# 2_-MCU_LPC1778FBD144.net
KiCad netlist of a schematic drawn in Altium Designer
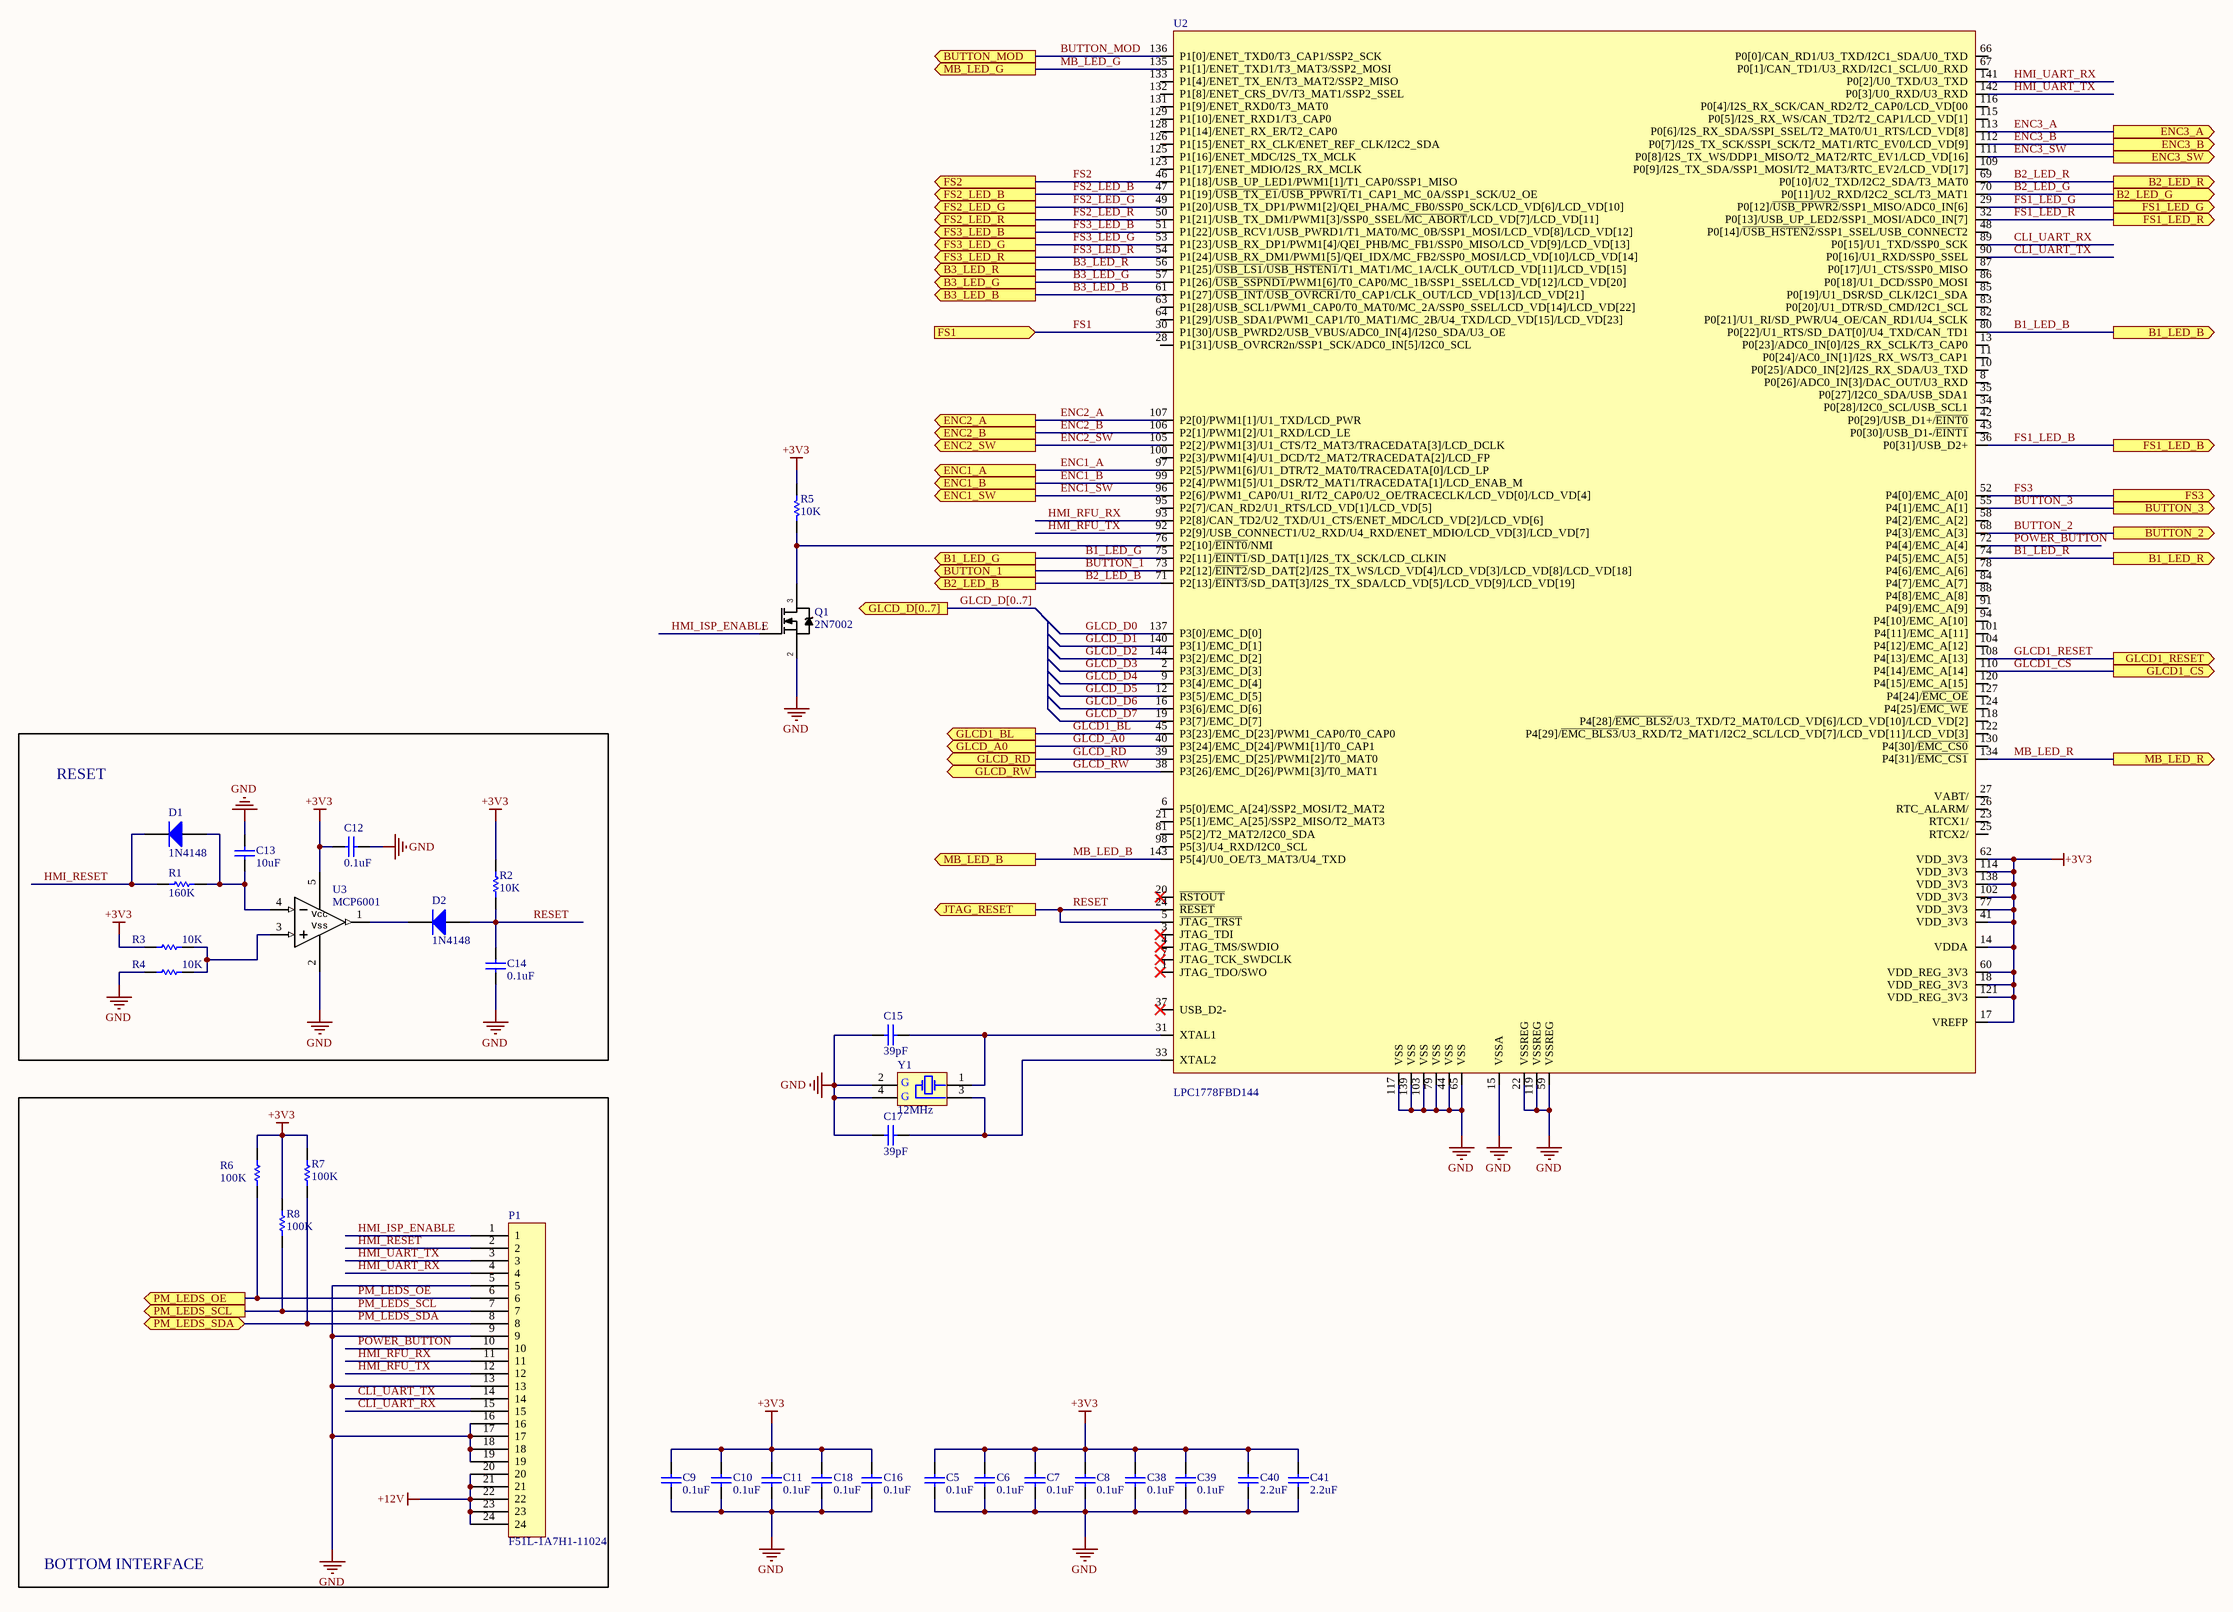
[diagram p0: [2]-MCU_LPC1778FBD144.SchDoc]

(export (version "E")
  (design (tool "Eeschema 10.0.6"))
  (components
    (comp (ref "C5")
      (value "0.1uF")
      (footprint "CAPC1608N")
      (description "CAP CER 0.1UF 25V X7R 0603")
      (fields (field (name "TOLERANCE") "10%") (field (name "VOLTAGE") "25V"))
      (libsource (lib "bitsnio") (part "CC0603KRX7R8BB104"))
    )
    (comp (ref "C6")
      (value "0.1uF")
      (footprint "CAPC1608N")
      (description "CAP CER 0.1UF 25V X7R 0603")
      (fields (field (name "TOLERANCE") "10%") (field (name "VOLTAGE") "25V"))
      (libsource (lib "bitsnio") (part "CC0603KRX7R8BB104"))
    )
    (comp (ref "C7")
      (value "0.1uF")
      (footprint "CAPC1608N")
      (description "CAP CER 0.1UF 25V X7R 0603")
      (fields (field (name "TOLERANCE") "10%") (field (name "VOLTAGE") "25V"))
      (libsource (lib "bitsnio") (part "CC0603KRX7R8BB104"))
    )
    (comp (ref "C8")
      (value "0.1uF")
      (footprint "CAPC1608N")
      (description "CAP CER 0.1UF 25V X7R 0603")
      (fields (field (name "TOLERANCE") "10%") (field (name "VOLTAGE") "25V"))
      (libsource (lib "bitsnio") (part "CC0603KRX7R8BB104"))
    )
    (comp (ref "C9")
      (value "0.1uF")
      (footprint "CAPC1608N")
      (description "CAP CER 0.1UF 25V X7R 0603")
      (fields (field (name "TOLERANCE") "10%") (field (name "VOLTAGE") "25V"))
      (libsource (lib "bitsnio") (part "CC0603KRX7R8BB104"))
    )
    (comp (ref "C10")
      (value "0.1uF")
      (footprint "CAPC1608N")
      (description "CAP CER 0.1UF 25V X7R 0603")
      (fields (field (name "TOLERANCE") "10%") (field (name "VOLTAGE") "25V"))
      (libsource (lib "bitsnio") (part "CC0603KRX7R8BB104"))
    )
    (comp (ref "C11")
      (value "0.1uF")
      (footprint "CAPC1608N")
      (description "CAP CER 0.1UF 25V X7R 0603")
      (fields (field (name "TOLERANCE") "10%") (field (name "VOLTAGE") "25V"))
      (libsource (lib "bitsnio") (part "CC0603KRX7R8BB104"))
    )
    (comp (ref "C12")
      (value "0.1uF")
      (footprint "CAPC1608N")
      (description "CAP CER 0.1UF 25V X7R 0603")
      (fields (field (name "TOLERANCE") "10%") (field (name "VOLTAGE") "25V"))
      (libsource (lib "bitsnio") (part "CC0603KRX7R8BB104"))
    )
    (comp (ref "C13")
      (value "10uF")
      (footprint "CAPC1608N")
      (description "CAP CER 10UF 10V X5R 0603")
      (fields (field (name "TOLERANCE") "10%") (field (name "VOLTAGE") "10V"))
      (libsource (lib "bitsnio") (part "GRM188R61A106KE69D"))
    )
    (comp (ref "C14")
      (value "0.1uF")
      (footprint "CAPC1608N")
      (description "CAP CER 0.1UF 25V X7R 0603")
      (fields (field (name "TOLERANCE") "10%") (field (name "VOLTAGE") "25V"))
      (libsource (lib "bitsnio") (part "CC0603KRX7R8BB104"))
    )
    (comp (ref "C15")
      (value "39pF")
      (footprint "CAPC1608N")
      (description "CAP CER 39PF 50V NP0 0603")
      (fields (field (name "TOLERANCE") "5%"))
      (libsource (lib "bitsnio") (part "C1608NP01H390J080AA"))
    )
    (comp (ref "C16")
      (value "0.1uF")
      (footprint "CAPC1608N")
      (description "CAP CER 0.1UF 25V X7R 0603")
      (fields (field (name "TOLERANCE") "10%") (field (name "VOLTAGE") "25V"))
      (libsource (lib "bitsnio") (part "CC0603KRX7R8BB104"))
    )
    (comp (ref "C17")
      (value "39pF")
      (footprint "CAPC1608N")
      (description "CAP CER 39PF 50V NP0 0603")
      (fields (field (name "TOLERANCE") "5%"))
      (libsource (lib "bitsnio") (part "C1608NP01H390J080AA"))
    )
    (comp (ref "C18")
      (value "0.1uF")
      (footprint "CAPC1608N")
      (description "CAP CER 0.1UF 25V X7R 0603")
      (fields (field (name "TOLERANCE") "10%") (field (name "VOLTAGE") "25V"))
      (libsource (lib "bitsnio") (part "CC0603KRX7R8BB104"))
    )
    (comp (ref "C38")
      (value "0.1uF")
      (footprint "CAPC1608N")
      (description "CAP CER 0.1UF 25V X7R 0603")
      (fields (field (name "TOLERANCE") "10%") (field (name "VOLTAGE") "25V"))
      (libsource (lib "bitsnio") (part "CC0603KRX7R8BB104"))
    )
    (comp (ref "C39")
      (value "0.1uF")
      (footprint "CAPC1608N")
      (description "CAP CER 0.1UF 25V X7R 0603")
      (fields (field (name "TOLERANCE") "10%") (field (name "VOLTAGE") "25V"))
      (libsource (lib "bitsnio") (part "CC0603KRX7R8BB104"))
    )
    (comp (ref "C40")
      (value "2.2uF")
      (footprint "CAPC1608N")
      (description "CAP CER 2.2UF 10V X5R 0603")
      (fields (field (name "MANUFACTURER PART NUMBER") "CL10A225KP8NNNC") (field (name "TOLERANCE") "10%"))
      (libsource (lib "bitsnio") (part "CL10A225KP8NNNC"))
    )
    (comp (ref "C41")
      (value "2.2uF")
      (footprint "CAPC1608N")
      (description "CAP CER 2.2UF 10V X5R 0603")
      (fields (field (name "MANUFACTURER PART NUMBER") "CL10A225KP8NNNC") (field (name "TOLERANCE") "10%"))
      (libsource (lib "bitsnio") (part "CL10A225KP8NNNC"))
    )
    (comp (ref "D1")
      (value "1N4148")
      (footprint "SOD-323")
      (description "DIODE SWITCHING 75V 0.15A SOD323")
      (fields (field (name "VOLTAGE") "75V"))
      (libsource (lib "bitsnio") (part "1N4148WS-7-F"))
    )
    (comp (ref "D2")
      (value "1N4148")
      (footprint "SOD-323")
      (description "DIODE SWITCHING 75V 0.15A SOD323")
      (fields (field (name "VOLTAGE") "75V"))
      (libsource (lib "bitsnio") (part "1N4148WS-7-F"))
    )
    (comp (ref "P1")
      (value "F51L-1A7H1-11024")
      (footprint "F51L-1A7H1-11024")
      (description "FLEX CONNECTOR, 1.00MM PITCH, HE")
      (libsource (lib "bitsnio") (part "F51L-1A7H1-11024"))
    )
    (comp (ref "Q1")
      (value "2N7002")
      (footprint "SOT23-3N")
      (description "MOSFET N-CH 60V 115MA SOT-23")
      (fields (field (name "VOLTAGE") "60V"))
      (libsource (lib "bitsnio") (part "2N7002"))
    )
    (comp (ref "R1")
      (value "160K")
      (footprint "RESC1608N")
      (description "RES SMD 160K OHM 5% 1/10W 0603")
      (fields (field (name "TOLERANCE") "5%"))
      (libsource (lib "bitsnio") (part "RMCF0603JT160K"))
    )
    (comp (ref "R2")
      (value "10K")
      (footprint "RESC1608N")
      (description "RES SMD 10K OHM 5% 1/10W 0603")
      (fields (field (name "TOLERANCE") "5%"))
      (libsource (lib "bitsnio") (part "AC0603JR-0710KL"))
    )
    (comp (ref "R3")
      (value "10K")
      (footprint "RESC1608N")
      (description "RES SMD 10K OHM 5% 1/10W 0603")
      (fields (field (name "TOLERANCE") "5%"))
      (libsource (lib "bitsnio") (part "AC0603JR-0710KL"))
    )
    (comp (ref "R4")
      (value "10K")
      (footprint "RESC1608N")
      (description "RES SMD 10K OHM 5% 1/10W 0603")
      (fields (field (name "TOLERANCE") "5%"))
      (libsource (lib "bitsnio") (part "AC0603JR-0710KL"))
    )
    (comp (ref "R5")
      (value "10K")
      (footprint "RESC1608N")
      (description "RES SMD 10K OHM 5% 1/10W 0603")
      (fields (field (name "TOLERANCE") "5%"))
      (libsource (lib "bitsnio") (part "AC0603JR-0710KL"))
    )
    (comp (ref "R6")
      (value "100K")
      (footprint "RESC1608N")
      (description "RES SMD 100K OHM 5% 1/4W 0603")
      (fields (field (name "TOLERANCE") "5%"))
      (libsource (lib "bitsnio") (part "ESR03EZPJ104"))
    )
    (comp (ref "R7")
      (value "100K")
      (footprint "RESC1608N")
      (description "RES SMD 100K OHM 5% 1/4W 0603")
      (fields (field (name "TOLERANCE") "5%"))
      (libsource (lib "bitsnio") (part "ESR03EZPJ104"))
    )
    (comp (ref "R8")
      (value "100K")
      (footprint "RESC1608N")
      (description "RES SMD 100K OHM 5% 1/4W 0603")
      (fields (field (name "TOLERANCE") "5%"))
      (libsource (lib "bitsnio") (part "ESR03EZPJ104"))
    )
    (comp (ref "U2")
      (value "LPC1778FBD144")
      (footprint "LQFP144-SOT486-1")
      (description "IC MCU 32BIT 512KB FLASH 144LQFP")
      (fields (field (name "MANUFACTURER PART NUMBER") "LPC1778FBD144,551"))
      (libsource (lib "bitsnio") (part "LPC1778FBD144,551"))
    )
    (comp (ref "U3")
      (value "MCP6001")
      (footprint "SOT23-5N")
      (description "IC OPAMP GP 1MHZ RRO SOT23-5")
      (fields (field (name "VOLTAGE") "6V"))
      (libsource (lib "bitsnio") (part "IC_MCP6001T-I/OT"))
    )
    (comp (ref "Y1")
      (value "12MHz")
      (footprint "ECS-120-20-30B-AGL-TR")
      (description "CRYSTAL 12MHZ 20PF SMD")
      (fields (field (name "MANUFACTURER PART NUMBER") "ECS-120-20-30B-AGL-TR"))
      (libsource (lib "bitsnio") (part "ECS-120-20-30B-AGL-TR"))
    )
  )
  (nets
    (net (code "1") (name "+3V3") (class "Default")
      (node (ref "C10") (pin "2") (pinfunction "2_2") (pintype "passive"))
      (node (ref "C11") (pin "2") (pinfunction "2_2") (pintype "passive"))
      (node (ref "C12") (pin "2") (pinfunction "2_2") (pintype "passive"))
      (node (ref "C16") (pin "2") (pinfunction "2_2") (pintype "passive"))
      (node (ref "C18") (pin "2") (pinfunction "2_2") (pintype "passive"))
      (node (ref "C38") (pin "2") (pinfunction "2_2") (pintype "passive"))
      (node (ref "C39") (pin "2") (pinfunction "2_2") (pintype "passive"))
      (node (ref "C40") (pin "2") (pinfunction "2_2") (pintype "passive"))
      (node (ref "C41") (pin "2") (pinfunction "2_2") (pintype "passive"))
      (node (ref "C5") (pin "2") (pinfunction "2_2") (pintype "passive"))
      (node (ref "C6") (pin "2") (pinfunction "2_2") (pintype "passive"))
      (node (ref "C7") (pin "2") (pinfunction "2_2") (pintype "passive"))
      (node (ref "C8") (pin "2") (pinfunction "2_2") (pintype "passive"))
      (node (ref "C9") (pin "2") (pinfunction "2_2") (pintype "passive"))
      (node (ref "R2") (pin "1") (pinfunction "1_1") (pintype "passive"))
      (node (ref "R3") (pin "2") (pinfunction "2_2") (pintype "passive"))
      (node (ref "R5") (pin "1") (pinfunction "1_1") (pintype "passive"))
      (node (ref "R6") (pin "2") (pinfunction "2_2") (pintype "passive"))
      (node (ref "R7") (pin "2") (pinfunction "2_2") (pintype "passive"))
      (node (ref "R8") (pin "2") (pinfunction "2_2") (pintype "passive"))
      (node (ref "U2") (pin "102") (pinfunction "VDD_3V3_102") (pintype "passive"))
      (node (ref "U2") (pin "114") (pinfunction "VDD_3V3_114") (pintype "passive"))
      (node (ref "U2") (pin "121") (pinfunction "VDD_REG_3V3_121") (pintype "passive"))
      (node (ref "U2") (pin "138") (pinfunction "VDD_3V3_138") (pintype "passive"))
      (node (ref "U2") (pin "14") (pinfunction "VDDA_14") (pintype "passive"))
      (node (ref "U2") (pin "17") (pinfunction "VREFP_17") (pintype "passive"))
      (node (ref "U2") (pin "18") (pinfunction "VDD_REG_3V3_18") (pintype "passive"))
      (node (ref "U2") (pin "41") (pinfunction "VDD_3V3_41") (pintype "passive"))
      (node (ref "U2") (pin "60") (pinfunction "VDD_REG_3V3_60") (pintype "passive"))
      (node (ref "U2") (pin "62") (pinfunction "VDD_3V3_62") (pintype "passive"))
      (node (ref "U2") (pin "77") (pinfunction "VDD_3V3_77") (pintype "passive"))
      (node (ref "U3") (pin "5") (pinfunction "VCC_5") (pintype "power_in"))
    )
    (net (code "2") (name "+12V") (class "Default")
      (node (ref "P1") (pin "20") (pinfunction "20_20") (pintype "passive"))
      (node (ref "P1") (pin "21") (pinfunction "21_21") (pintype "passive"))
      (node (ref "P1") (pin "22") (pinfunction "22_22") (pintype "passive"))
      (node (ref "P1") (pin "23") (pinfunction "23_23") (pintype "passive"))
      (node (ref "P1") (pin "24") (pinfunction "24_24") (pintype "passive"))
    )
    (net (code "3") (name "/B1_LED_B") (class "Default")
      (node (ref "U2") (pin "80") (pinfunction "P0[22]/U1_RTS/SD_DAT[0]/U4_TXD/CAN_TD1_80") (pintype "passive"))
    )
    (net (code "4") (name "/B1_LED_G") (class "Default")
      (node (ref "U2") (pin "75") (pinfunction "P2[11]/~{EINT1}/SD_DAT[1]/I2S_TX_SCK/LCD_CLKIN_75") (pintype "passive"))
    )
    (net (code "5") (name "/B1_LED_R") (class "Default")
      (node (ref "U2") (pin "74") (pinfunction "P4[5]/EMC_A[5]_74") (pintype "passive"))
    )
    (net (code "6") (name "/B2_LED_B") (class "Default")
      (node (ref "U2") (pin "71") (pinfunction "P2[13]/~{EINT3}/SD_DAT[3]/I2S_TX_SDA/LCD_VD[5]/LCD_VD[9]/LCD_VD[19]_71") (pintype "passive"))
    )
    (net (code "7") (name "/B2_LED_G") (class "Default")
      (node (ref "U2") (pin "70") (pinfunction "P0[11]/U2_RXD/I2C2_SCL/T3_MAT1_70") (pintype "passive"))
    )
    (net (code "8") (name "/B2_LED_R") (class "Default")
      (node (ref "U2") (pin "69") (pinfunction "P0[10]/U2_TXD/I2C2_SDA/T3_MAT0_69") (pintype "passive"))
    )
    (net (code "9") (name "/B3_LED_B") (class "Default")
      (node (ref "U2") (pin "61") (pinfunction "P1[27]/~{USB_INT}/~{USB_OVRCR1}/T0_CAP1/CLK_OUT/LCD_VD[13]/LCD_VD[21]_61") (pintype "passive"))
    )
    (net (code "10") (name "/B3_LED_G") (class "Default")
      (node (ref "U2") (pin "57") (pinfunction "P1[26]/~{USB_SSPND1}/PWM1[6]/T0_CAP0/MC_1B/SSP1_SSEL/LCD_VD[12]/LCD_VD[20]_57") (pintype "passive"))
    )
    (net (code "11") (name "/B3_LED_R") (class "Default")
      (node (ref "U2") (pin "56") (pinfunction "P1[25]/~{USB_LS1}/~{USB_HSTEN1}/T1_MAT1/MC_1A/CLK_OUT/LCD_VD[11]/LCD_VD[15]_56") (pintype "passive"))
    )
    (net (code "12") (name "/BUTTON_1") (class "Default")
      (node (ref "U2") (pin "73") (pinfunction "P2[12]/~{EINT2}/SD_DAT[2]/I2S_TX_WS/LCD_VD[4]/LCD_VD[3]/LCD_VD[8]/LCD_VD[18]_73") (pintype "passive"))
    )
    (net (code "13") (name "/BUTTON_2") (class "Default")
      (node (ref "U2") (pin "68") (pinfunction "P4[3]/EMC_A[3]_68") (pintype "passive"))
    )
    (net (code "14") (name "/BUTTON_3") (class "Default")
      (node (ref "U2") (pin "55") (pinfunction "P4[1]/EMC_A[1]_55") (pintype "passive"))
    )
    (net (code "15") (name "/BUTTON_MOD") (class "Default")
      (node (ref "U2") (pin "136") (pinfunction "P1[0]/ENET_TXD0/T3_CAP1/SSP2_SCK_136") (pintype "passive"))
    )
    (net (code "16") (name "/CLI_UART_RX") (class "Default")
      (node (ref "P1") (pin "15") (pinfunction "15_15") (pintype "passive"))
      (node (ref "U2") (pin "89") (pinfunction "P0[15]/U1_TXD/SSP0_SCK_89") (pintype "passive"))
    )
    (net (code "17") (name "/CLI_UART_TX") (class "Default")
      (node (ref "P1") (pin "14") (pinfunction "14_14") (pintype "passive"))
      (node (ref "U2") (pin "90") (pinfunction "P0[16]/U1_RXD/SSP0_SSEL_90") (pintype "passive"))
    )
    (net (code "18") (name "/ENC1_A") (class "Default")
      (node (ref "U2") (pin "97") (pinfunction "P2[5]/PWM1[6]/U1_DTR/T2_MAT0/TRACEDATA[0]/LCD_LP_97") (pintype "passive"))
    )
    (net (code "19") (name "/ENC1_B") (class "Default")
      (node (ref "U2") (pin "99") (pinfunction "P2[4]/PWM1[5]/U1_DSR/T2_MAT1/TRACEDATA[1]/LCD_ENAB_M_99") (pintype "passive"))
    )
    (net (code "20") (name "/ENC1_SW") (class "Default")
      (node (ref "U2") (pin "96") (pinfunction "P2[6]/PWM1_CAP0/U1_RI/T2_CAP0/U2_OE/TRACECLK/LCD_VD[0]/LCD_VD[4]_96") (pintype "passive"))
    )
    (net (code "21") (name "/ENC2_A") (class "Default")
      (node (ref "U2") (pin "107") (pinfunction "P2[0]/PWM1[1]/U1_TXD/LCD_PWR_107") (pintype "passive"))
    )
    (net (code "22") (name "/ENC2_B") (class "Default")
      (node (ref "U2") (pin "106") (pinfunction "P2[1]/PWM1[2]/U1_RXD/LCD_LE_106") (pintype "passive"))
    )
    (net (code "23") (name "/ENC2_SW") (class "Default")
      (node (ref "U2") (pin "105") (pinfunction "P2[2]/PWM1[3]/U1_CTS/T2_MAT3/TRACEDATA[3]/LCD_DCLK_105") (pintype "passive"))
    )
    (net (code "24") (name "/ENC3_A") (class "Default")
      (node (ref "U2") (pin "113") (pinfunction "P0[6]/I2S_RX_SDA/SSPI_SSEL/T2_MAT0/U1_RTS/LCD_VD[8]_113") (pintype "passive"))
    )
    (net (code "25") (name "/ENC3_B") (class "Default")
      (node (ref "U2") (pin "112") (pinfunction "P0[7]/I2S_TX_SCK/SSPI_SCK/T2_MAT1/RTC_EV0/LCD_VD[9]_112") (pintype "passive"))
    )
    (net (code "26") (name "/ENC3_SW") (class "Default")
      (node (ref "U2") (pin "111") (pinfunction "P0[8]/I2S_TX_WS/DDP1_MISO/T2_MAT2/RTC_EV1/LCD_VD[16]_111") (pintype "passive"))
    )
    (net (code "27") (name "/FS1") (class "Default")
      (node (ref "U2") (pin "30") (pinfunction "P1[30]/USB_PWRD2/USB_VBUS/ADC0_IN[4]/I2S0_SDA/U3_OE_30") (pintype "passive"))
    )
    (net (code "28") (name "/FS1_LED_B") (class "Default")
      (node (ref "U2") (pin "36") (pinfunction "P0[31]/USB_D2+_36") (pintype "passive"))
    )
    (net (code "29") (name "/FS1_LED_G") (class "Default")
      (node (ref "U2") (pin "29") (pinfunction "P0[12]/~{USB_PPWR2}/SSP1_MISO/ADC0_IN[6]_29") (pintype "passive"))
    )
    (net (code "30") (name "/FS1_LED_R") (class "Default")
      (node (ref "U2") (pin "32") (pinfunction "P0[13]/USB_UP_LED2/SSP1_MOSI/ADC0_IN[7]_32") (pintype "passive"))
    )
    (net (code "31") (name "/FS2") (class "Default")
      (node (ref "U2") (pin "46") (pinfunction "P1[18]/USB_UP_LED1/PWM1[1]/T1_CAP0/SSP1_MISO_46") (pintype "passive"))
    )
    (net (code "32") (name "/FS2_LED_B") (class "Default")
      (node (ref "U2") (pin "47") (pinfunction "P1[19]/~{USB_TX_E1}/~{USB_PPWR1}/T1_CAP1_MC_0A/SSP1_SCK/U2_OE_47") (pintype "passive"))
    )
    (net (code "33") (name "/FS2_LED_G") (class "Default")
      (node (ref "U2") (pin "49") (pinfunction "P1[20]/USB_TX_DP1/PWM1[2]/QEI_PHA/MC_FB0/SSP0_SCK/LCD_VD[6]/LCD_VD[10]_49") (pintype "passive"))
    )
    (net (code "34") (name "/FS2_LED_R") (class "Default")
      (node (ref "U2") (pin "50") (pinfunction "P1[21]/USB_TX_DM1/PWM1[3]/SSP0_SSEL/~{MC_ABORT}/LCD_VD[7]/LCD_VD[11]_50") (pintype "passive"))
    )
    (net (code "35") (name "/FS3") (class "Default")
      (node (ref "U2") (pin "52") (pinfunction "P4[0]/EMC_A[0]_52") (pintype "passive"))
    )
    (net (code "36") (name "/FS3_LED_B") (class "Default")
      (node (ref "U2") (pin "51") (pinfunction "P1[22]/USB_RCV1/USB_PWRD1/T1_MAT0/MC_0B/SSP1_MOSI/LCD_VD[8]/LCD_VD[12]_51") (pintype "passive"))
    )
    (net (code "37") (name "/FS3_LED_G") (class "Default")
      (node (ref "U2") (pin "53") (pinfunction "P1[23]/USB_RX_DP1/PWM1[4]/QEI_PHB/MC_FB1/SSP0_MISO/LCD_VD[9]/LCD_VD[13]_53") (pintype "passive"))
    )
    (net (code "38") (name "/FS3_LED_R") (class "Default")
      (node (ref "U2") (pin "54") (pinfunction "P1[24]/USB_RX_DM1/PWM1[5]/QEI_IDX/MC_FB2/SSP0_MOSI/LCD_VD[10]/LCD_VD[14]_54") (pintype "passive"))
    )
    (net (code "39") (name "/GLCD1_BL") (class "Default")
      (node (ref "U2") (pin "45") (pinfunction "P3[23]/EMC_D[23]/PWM1_CAP0/T0_CAP0_45") (pintype "passive"))
    )
    (net (code "40") (name "/GLCD1_CS") (class "Default")
      (node (ref "U2") (pin "110") (pinfunction "P4[14]/EMC_A[14]_110") (pintype "passive"))
    )
    (net (code "41") (name "/GLCD1_RESET") (class "Default")
      (node (ref "U2") (pin "108") (pinfunction "P4[13]/EMC_A[13]_108") (pintype "passive"))
    )
    (net (code "42") (name "/GLCD_A0") (class "Default")
      (node (ref "U2") (pin "40") (pinfunction "P3[24]/EMC_D[24]/PWM1[1]/T0_CAP1_40") (pintype "passive"))
    )
    (net (code "43") (name "/GLCD_D0") (class "Default")
      (node (ref "U2") (pin "137") (pinfunction "P3[0]/EMC_D[0]_137") (pintype "passive"))
    )
    (net (code "44") (name "/GLCD_D1") (class "Default")
      (node (ref "U2") (pin "140") (pinfunction "P3[1]/EMC_D[1]_140") (pintype "passive"))
    )
    (net (code "45") (name "/GLCD_D2") (class "Default")
      (node (ref "U2") (pin "144") (pinfunction "P3[2]/EMC_D[2]_144") (pintype "passive"))
    )
    (net (code "46") (name "/GLCD_D3") (class "Default")
      (node (ref "U2") (pin "2") (pinfunction "P3[3]/EMC_D[3]_2") (pintype "passive"))
    )
    (net (code "47") (name "/GLCD_D4") (class "Default")
      (node (ref "U2") (pin "9") (pinfunction "P3[4]/EMC_D[4]_9") (pintype "passive"))
    )
    (net (code "48") (name "/GLCD_D5") (class "Default")
      (node (ref "U2") (pin "12") (pinfunction "P3[5]/EMC_D[5]_12") (pintype "passive"))
    )
    (net (code "49") (name "/GLCD_D6") (class "Default")
      (node (ref "U2") (pin "16") (pinfunction "P3[6]/EMC_D[6]_16") (pintype "passive"))
    )
    (net (code "50") (name "/GLCD_D7") (class "Default")
      (node (ref "U2") (pin "19") (pinfunction "P3[7]/EMC_D[7]_19") (pintype "passive"))
    )
    (net (code "52") (name "/GLCD_RD") (class "Default")
      (node (ref "U2") (pin "39") (pinfunction "P3[25]/EMC_D[25]/PWM1[2]/T0_MAT0_39") (pintype "passive"))
    )
    (net (code "53") (name "/GLCD_RW") (class "Default")
      (node (ref "U2") (pin "38") (pinfunction "P3[26]/EMC_D[26]/PWM1[3]/T0_MAT1_38") (pintype "passive"))
    )
    (net (code "54") (name "/HMI_ISP_ENABLE") (class "Default")
      (node (ref "P1") (pin "1") (pinfunction "1_1") (pintype "passive"))
      (node (ref "Q1") (pin "1") (pinfunction "G_1") (pintype "passive"))
    )
    (net (code "55") (name "/HMI_RESET") (class "Default")
      (node (ref "D1") (pin "1") (pinfunction "K_1") (pintype "passive"))
      (node (ref "P1") (pin "2") (pinfunction "2_2") (pintype "passive"))
      (node (ref "R1") (pin "1") (pinfunction "1_1") (pintype "passive"))
    )
    (net (code "56") (name "/HMI_RFU_RX") (class "Default")
      (node (ref "P1") (pin "11") (pinfunction "11_11") (pintype "passive"))
      (node (ref "U2") (pin "93") (pinfunction "P2[8]/CAN_TD2/U2_TXD/U1_CTS/ENET_MDC/LCD_VD[2]/LCD_VD[6]_93") (pintype "passive"))
    )
    (net (code "57") (name "/HMI_RFU_TX") (class "Default")
      (node (ref "P1") (pin "12") (pinfunction "12_12") (pintype "passive"))
      (node (ref "U2") (pin "92") (pinfunction "P2[9]/USB_CONNECT1/U2_RXD/U4_RXD/ENET_MDIO/LCD_VD[3]/LCD_VD[7]_92") (pintype "passive"))
    )
    (net (code "58") (name "/HMI_UART_RX") (class "Default")
      (node (ref "P1") (pin "4") (pinfunction "4_4") (pintype "passive"))
      (node (ref "U2") (pin "141") (pinfunction "P0[2]/U0_TXD/U3_TXD_141") (pintype "passive"))
    )
    (net (code "59") (name "/HMI_UART_TX") (class "Default")
      (node (ref "P1") (pin "3") (pinfunction "3_3") (pintype "passive"))
      (node (ref "U2") (pin "142") (pinfunction "P0[3]/U0_RXD/U3_RXD_142") (pintype "passive"))
    )
    (net (code "60") (name "/MB_LED_B") (class "Default")
      (node (ref "U2") (pin "143") (pinfunction "P5[4]/U0_OE/T3_MAT3/U4_TXD_143") (pintype "passive"))
    )
    (net (code "61") (name "/MB_LED_G") (class "Default")
      (node (ref "U2") (pin "135") (pinfunction "P1[1]/ENET_TXD1/T3_MAT3/SSP2_MOSI_135") (pintype "passive"))
    )
    (net (code "62") (name "/MB_LED_R") (class "Default")
      (node (ref "U2") (pin "134") (pinfunction "P4[31]/~{EMC_CS1}_134") (pintype "passive"))
    )
    (net (code "63") (name "/PM_LEDS_OE") (class "Default")
      (node (ref "P1") (pin "6") (pinfunction "6_6") (pintype "passive"))
      (node (ref "R6") (pin "1") (pinfunction "1_1") (pintype "passive"))
    )
    (net (code "64") (name "/PM_LEDS_SCL") (class "Default")
      (node (ref "P1") (pin "7") (pinfunction "7_7") (pintype "passive"))
      (node (ref "R8") (pin "1") (pinfunction "1_1") (pintype "passive"))
    )
    (net (code "65") (name "/PM_LEDS_SDA") (class "Default")
      (node (ref "P1") (pin "8") (pinfunction "8_8") (pintype "passive"))
      (node (ref "R7") (pin "1") (pinfunction "1_1") (pintype "passive"))
    )
    (net (code "66") (name "/POWER_BUTTON") (class "Default")
      (node (ref "P1") (pin "10") (pinfunction "10_10") (pintype "passive"))
      (node (ref "U2") (pin "72") (pinfunction "P4[4]/EMC_A[4]_72") (pintype "passive"))
    )
    (net (code "67") (name "/RESET") (class "Default")
      (node (ref "C14") (pin "1") (pinfunction "1_1") (pintype "passive"))
      (node (ref "D2") (pin "2") (pinfunction "A_2") (pintype "passive"))
      (node (ref "R2") (pin "2") (pinfunction "2_2") (pintype "passive"))
      (node (ref "U2") (pin "24") (pinfunction "~{RESET}_24") (pintype "passive"))
      (node (ref "U2") (pin "5") (pinfunction "~{JTAG_TRST}_5") (pintype "passive"))
    )
    (net (code "68") (name "GND") (class "Default")
      (node (ref "C10") (pin "1") (pinfunction "1_1") (pintype "passive"))
      (node (ref "C11") (pin "1") (pinfunction "1_1") (pintype "passive"))
      (node (ref "C12") (pin "1") (pinfunction "1_1") (pintype "passive"))
      (node (ref "C13") (pin "1") (pinfunction "1_1") (pintype "passive"))
      (node (ref "C14") (pin "2") (pinfunction "2_2") (pintype "passive"))
      (node (ref "C15") (pin "2") (pinfunction "2_2") (pintype "passive"))
      (node (ref "C16") (pin "1") (pinfunction "1_1") (pintype "passive"))
      (node (ref "C17") (pin "1") (pinfunction "1_1") (pintype "passive"))
      (node (ref "C18") (pin "1") (pinfunction "1_1") (pintype "passive"))
      (node (ref "C38") (pin "1") (pinfunction "1_1") (pintype "passive"))
      (node (ref "C39") (pin "1") (pinfunction "1_1") (pintype "passive"))
      (node (ref "C40") (pin "1") (pinfunction "1_1") (pintype "passive"))
      (node (ref "C41") (pin "1") (pinfunction "1_1") (pintype "passive"))
      (node (ref "C5") (pin "1") (pinfunction "1_1") (pintype "passive"))
      (node (ref "C6") (pin "1") (pinfunction "1_1") (pintype "passive"))
      (node (ref "C7") (pin "1") (pinfunction "1_1") (pintype "passive"))
      (node (ref "C8") (pin "1") (pinfunction "1_1") (pintype "passive"))
      (node (ref "C9") (pin "1") (pinfunction "1_1") (pintype "passive"))
      (node (ref "P1") (pin "13") (pinfunction "13_13") (pintype "passive"))
      (node (ref "P1") (pin "16") (pinfunction "16_16") (pintype "passive"))
      (node (ref "P1") (pin "17") (pinfunction "17_17") (pintype "passive"))
      (node (ref "P1") (pin "18") (pinfunction "18_18") (pintype "passive"))
      (node (ref "P1") (pin "19") (pinfunction "19_19") (pintype "passive"))
      (node (ref "P1") (pin "5") (pinfunction "5_5") (pintype "passive"))
      (node (ref "P1") (pin "9") (pinfunction "9_9") (pintype "passive"))
      (node (ref "Q1") (pin "2") (pinfunction "S_2") (pintype "passive"))
      (node (ref "R4") (pin "2") (pinfunction "2_2") (pintype "passive"))
      (node (ref "U2") (pin "103") (pinfunction "VSS_103") (pintype "passive"))
      (node (ref "U2") (pin "117") (pinfunction "VSS_117") (pintype "passive"))
      (node (ref "U2") (pin "119") (pinfunction "VSSREG_119") (pintype "passive"))
      (node (ref "U2") (pin "139") (pinfunction "VSS_139") (pintype "passive"))
      (node (ref "U2") (pin "15") (pinfunction "VSSA_15") (pintype "passive"))
      (node (ref "U2") (pin "22") (pinfunction "VSSREG_22") (pintype "passive"))
      (node (ref "U2") (pin "44") (pinfunction "VSS_44") (pintype "passive"))
      (node (ref "U2") (pin "59") (pinfunction "VSSREG_59") (pintype "passive"))
      (node (ref "U2") (pin "65") (pinfunction "VSS_65") (pintype "passive"))
      (node (ref "U2") (pin "79") (pinfunction "VSS_79") (pintype "passive"))
      (node (ref "U3") (pin "2") (pinfunction "VSS_2") (pintype "power_in"))
      (node (ref "Y1") (pin "2") (pinfunction "G_2") (pintype "passive"))
      (node (ref "Y1") (pin "4") (pinfunction "G_4") (pintype "passive"))
    )
    (net (code "69") (name "Net-(D1-A)") (class "Default")
      (node (ref "C13") (pin "2") (pinfunction "2_2") (pintype "passive"))
      (node (ref "D1") (pin "2") (pinfunction "A_2") (pintype "passive"))
      (node (ref "R1") (pin "2") (pinfunction "2_2") (pintype "passive"))
      (node (ref "U3") (pin "4") (pinfunction "IN-_4") (pintype "input"))
    )
    (net (code "70") (name "Net-(D2-K)") (class "Default")
      (node (ref "D2") (pin "1") (pinfunction "K_1") (pintype "passive"))
      (node (ref "U3") (pin "1") (pinfunction "OUT_1") (pintype "output"))
    )
    (net (code "71") (name "Net-(Q1-D)") (class "Default")
      (node (ref "Q1") (pin "3") (pinfunction "D_3") (pintype "passive"))
      (node (ref "R5") (pin "2") (pinfunction "2_2") (pintype "passive"))
      (node (ref "U2") (pin "76") (pinfunction "P2[10]/~{EINT0}/NMI_76") (pintype "passive"))
    )
    (net (code "72") (name "Net-(U2-XTAL1)") (class "Default")
      (node (ref "C15") (pin "1") (pinfunction "1_1") (pintype "passive"))
      (node (ref "U2") (pin "31") (pinfunction "XTAL1_31") (pintype "passive"))
      (node (ref "Y1") (pin "1") (pinfunction "OSC1_1") (pintype "passive"))
    )
    (net (code "73") (name "Net-(U2-XTAL2)") (class "Default")
      (node (ref "C17") (pin "2") (pinfunction "2_2") (pintype "passive"))
      (node (ref "U2") (pin "33") (pinfunction "XTAL2_33") (pintype "passive"))
      (node (ref "Y1") (pin "3") (pinfunction "OSC2_3") (pintype "passive"))
    )
    (net (code "74") (name "Net-(U3-IN+)") (class "Default")
      (node (ref "R3") (pin "1") (pinfunction "1_1") (pintype "passive"))
      (node (ref "R4") (pin "1") (pinfunction "1_1") (pintype "passive"))
      (node (ref "U3") (pin "3") (pinfunction "IN+_3") (pintype "input"))
    )
    (net (code "75") (name "unconnected-(U2-JTAG_TCK_SWDCLK-Pad7)") (class "Default")
      (node (ref "U2") (pin "7") (pinfunction "JTAG_TCK_SWDCLK_7") (pintype "passive+no_connect"))
    )
    (net (code "76") (name "unconnected-(U2-JTAG_TDI-Pad3)") (class "Default")
      (node (ref "U2") (pin "3") (pinfunction "JTAG_TDI_3") (pintype "passive+no_connect"))
    )
    (net (code "77") (name "unconnected-(U2-JTAG_TDO{slash}SWO-Pad1)") (class "Default")
      (node (ref "U2") (pin "1") (pinfunction "JTAG_TDO/SWO_1") (pintype "passive+no_connect"))
    )
    (net (code "78") (name "unconnected-(U2-JTAG_TMS{slash}SWDIO-Pad4)") (class "Default")
      (node (ref "U2") (pin "4") (pinfunction "JTAG_TMS/SWDIO_4") (pintype "passive+no_connect"))
    )
    (net (code "79") (name "unconnected-(U2-P0[0]{slash}CAN_RD1{slash}U3_TXD{slash}I2C1_SDA{slash}U0_TXD-Pad66)") (class "Default")
      (node (ref "U2") (pin "66") (pinfunction "P0[0]/CAN_RD1/U3_TXD/I2C1_SDA/U0_TXD_66") (pintype "passive"))
    )
    (net (code "80") (name "unconnected-(U2-P0[1]{slash}CAN_TD1{slash}U3_RXD{slash}I2C1_SCL{slash}U0_RXD-Pad67)") (class "Default")
      (node (ref "U2") (pin "67") (pinfunction "P0[1]/CAN_TD1/U3_RXD/I2C1_SCL/U0_RXD_67") (pintype "passive"))
    )
    (net (code "81") (name "unconnected-(U2-P0[4]{slash}I2S_RX_SCK{slash}CAN_RD2{slash}T2_CAP0{slash}LCD_VD[00-Pad116)") (class "Default")
      (node (ref "U2") (pin "116") (pinfunction "P0[4]/I2S_RX_SCK/CAN_RD2/T2_CAP0/LCD_VD[00_116") (pintype "passive"))
    )
    (net (code "82") (name "unconnected-(U2-P0[5]{slash}I2S_RX_WS{slash}CAN_TD2{slash}T2_CAP1{slash}LCD_VD[1]-Pad115)") (class "Default")
      (node (ref "U2") (pin "115") (pinfunction "P0[5]/I2S_RX_WS/CAN_TD2/T2_CAP1/LCD_VD[1]_115") (pintype "passive"))
    )
    (net (code "83") (name "unconnected-(U2-P0[9]{slash}I2S_TX_SDA{slash}SSP1_MOSI{slash}T2_MAT3{slash}RTC_EV2{slash}LCD_VD[17]-Pad109)") (class "Default")
      (node (ref "U2") (pin "109") (pinfunction "P0[9]/I2S_TX_SDA/SSP1_MOSI/T2_MAT3/RTC_EV2/LCD_VD[17]_109") (pintype "passive"))
    )
    (net (code "84") (name "unconnected-(U2-P0[14]{slash}~{USB_HSTEN2}{slash}SSP1_SSEL{slash}USB_CONNECT2-Pad48)") (class "Default")
      (node (ref "U2") (pin "48") (pinfunction "P0[14]/~{USB_HSTEN2}/SSP1_SSEL/USB_CONNECT2_48") (pintype "passive"))
    )
    (net (code "85") (name "unconnected-(U2-P0[17]{slash}U1_CTS{slash}SSP0_MISO-Pad87)") (class "Default")
      (node (ref "U2") (pin "87") (pinfunction "P0[17]/U1_CTS/SSP0_MISO_87") (pintype "passive"))
    )
    (net (code "86") (name "unconnected-(U2-P0[18]{slash}U1_DCD{slash}SSP0_MOSI-Pad86)") (class "Default")
      (node (ref "U2") (pin "86") (pinfunction "P0[18]/U1_DCD/SSP0_MOSI_86") (pintype "passive"))
    )
    (net (code "87") (name "unconnected-(U2-P0[19]{slash}U1_DSR{slash}SD_CLK{slash}I2C1_SDA-Pad85)") (class "Default")
      (node (ref "U2") (pin "85") (pinfunction "P0[19]/U1_DSR/SD_CLK/I2C1_SDA_85") (pintype "passive"))
    )
    (net (code "88") (name "unconnected-(U2-P0[20]{slash}U1_DTR{slash}SD_CMD{slash}I2C1_SCL-Pad83)") (class "Default")
      (node (ref "U2") (pin "83") (pinfunction "P0[20]/U1_DTR/SD_CMD/I2C1_SCL_83") (pintype "passive"))
    )
    (net (code "89") (name "unconnected-(U2-P0[21]{slash}U1_RI{slash}SD_PWR{slash}U4_OE{slash}CAN_RD1{slash}U4_SCLK-Pad82)") (class "Default")
      (node (ref "U2") (pin "82") (pinfunction "P0[21]/U1_RI/SD_PWR/U4_OE/CAN_RD1/U4_SCLK_82") (pintype "passive"))
    )
    (net (code "90") (name "unconnected-(U2-P0[23]{slash}ADC0_IN[0]{slash}I2S_RX_SCLK{slash}T3_CAP0-Pad13)") (class "Default")
      (node (ref "U2") (pin "13") (pinfunction "P0[23]/ADC0_IN[0]/I2S_RX_SCLK/T3_CAP0_13") (pintype "passive"))
    )
    (net (code "91") (name "unconnected-(U2-P0[24]{slash}AC0_IN[1]{slash}I2S_RX_WS{slash}T3_CAP1-Pad11)") (class "Default")
      (node (ref "U2") (pin "11") (pinfunction "P0[24]/AC0_IN[1]/I2S_RX_WS/T3_CAP1_11") (pintype "passive"))
    )
    (net (code "92") (name "unconnected-(U2-P0[25]{slash}ADC0_IN[2]{slash}I2S_RX_SDA{slash}U3_TXD-Pad10)") (class "Default")
      (node (ref "U2") (pin "10") (pinfunction "P0[25]/ADC0_IN[2]/I2S_RX_SDA/U3_TXD_10") (pintype "passive"))
    )
    (net (code "93") (name "unconnected-(U2-P0[26]{slash}ADC0_IN[3]{slash}DAC_OUT{slash}U3_RXD-Pad8)") (class "Default")
      (node (ref "U2") (pin "8") (pinfunction "P0[26]/ADC0_IN[3]/DAC_OUT/U3_RXD_8") (pintype "passive"))
    )
    (net (code "94") (name "unconnected-(U2-P0[27]{slash}I2C0_SDA{slash}USB_SDA1-Pad35)") (class "Default")
      (node (ref "U2") (pin "35") (pinfunction "P0[27]/I2C0_SDA/USB_SDA1_35") (pintype "passive"))
    )
    (net (code "95") (name "unconnected-(U2-P0[28]{slash}I2C0_SCL{slash}USB_SCL1-Pad34)") (class "Default")
      (node (ref "U2") (pin "34") (pinfunction "P0[28]/I2C0_SCL/USB_SCL1_34") (pintype "passive"))
    )
    (net (code "96") (name "unconnected-(U2-P0[29]{slash}USB_D1+{slash}~{EINT0}-Pad42)") (class "Default")
      (node (ref "U2") (pin "42") (pinfunction "P0[29]/USB_D1+/~{EINT0}_42") (pintype "passive"))
    )
    (net (code "97") (name "unconnected-(U2-P0[30]{slash}USB_D1-{slash}~{EINT1}-Pad43)") (class "Default")
      (node (ref "U2") (pin "43") (pinfunction "P0[30]/USB_D1-/~{EINT1}_43") (pintype "passive"))
    )
    (net (code "98") (name "unconnected-(U2-P1[4]{slash}ENET_TX_EN{slash}T3_MAT2{slash}SSP2_MISO-Pad133)") (class "Default")
      (node (ref "U2") (pin "133") (pinfunction "P1[4]/ENET_TX_EN/T3_MAT2/SSP2_MISO_133") (pintype "passive"))
    )
    (net (code "99") (name "unconnected-(U2-P1[8]{slash}ENET_CRS_DV{slash}T3_MAT1{slash}SSP2_SSEL-Pad132)") (class "Default")
      (node (ref "U2") (pin "132") (pinfunction "P1[8]/ENET_CRS_DV/T3_MAT1/SSP2_SSEL_132") (pintype "passive"))
    )
    (net (code "100") (name "unconnected-(U2-P1[9]{slash}ENET_RXD0{slash}T3_MAT0-Pad131)") (class "Default")
      (node (ref "U2") (pin "131") (pinfunction "P1[9]/ENET_RXD0/T3_MAT0_131") (pintype "passive"))
    )
    (net (code "101") (name "unconnected-(U2-P1[10]{slash}ENET_RXD1{slash}T3_CAP0-Pad129)") (class "Default")
      (node (ref "U2") (pin "129") (pinfunction "P1[10]/ENET_RXD1/T3_CAP0_129") (pintype "passive"))
    )
    (net (code "102") (name "unconnected-(U2-P1[14]{slash}ENET_RX_ER{slash}T2_CAP0-Pad128)") (class "Default")
      (node (ref "U2") (pin "128") (pinfunction "P1[14]/ENET_RX_ER/T2_CAP0_128") (pintype "passive"))
    )
    (net (code "103") (name "unconnected-(U2-P1[15]{slash}ENET_RX_CLK{slash}ENET_REF_CLK{slash}I2C2_SDA-Pad126)") (class "Default")
      (node (ref "U2") (pin "126") (pinfunction "P1[15]/ENET_RX_CLK/ENET_REF_CLK/I2C2_SDA_126") (pintype "passive"))
    )
    (net (code "104") (name "unconnected-(U2-P1[16]{slash}ENET_MDC{slash}I2S_TX_MCLK-Pad125)") (class "Default")
      (node (ref "U2") (pin "125") (pinfunction "P1[16]/ENET_MDC/I2S_TX_MCLK_125") (pintype "passive"))
    )
    (net (code "105") (name "unconnected-(U2-P1[17]{slash}ENET_MDIO{slash}I2S_RX_MCLK-Pad123)") (class "Default")
      (node (ref "U2") (pin "123") (pinfunction "P1[17]/ENET_MDIO/I2S_RX_MCLK_123") (pintype "passive"))
    )
    (net (code "106") (name "unconnected-(U2-P1[28]{slash}USB_SCL1{slash}PWM1_CAP0{slash}T0_MAT0{slash}MC_2A{slash}SSP0_SSEL{slash}LCD_VD[14]{slash}LCD_VD[22]-Pad63)") (class "Default")
      (node (ref "U2") (pin "63") (pinfunction "P1[28]/USB_SCL1/PWM1_CAP0/T0_MAT0/MC_2A/SSP0_SSEL/LCD_VD[14]/LCD_VD[22]_63") (pintype "passive"))
    )
    (net (code "107") (name "unconnected-(U2-P1[29]{slash}USB_SDA1{slash}PWM1_CAP1{slash}T0_MAT1{slash}MC_2B{slash}U4_TXD{slash}LCD_VD[15]{slash}LCD_VD[23]-Pad64)") (class "Default")
      (node (ref "U2") (pin "64") (pinfunction "P1[29]/USB_SDA1/PWM1_CAP1/T0_MAT1/MC_2B/U4_TXD/LCD_VD[15]/LCD_VD[23]_64") (pintype "passive"))
    )
    (net (code "108") (name "unconnected-(U2-P1[31]{slash}USB_OVRCR2n{slash}SSP1_SCK{slash}ADC0_IN[5]{slash}I2C0_SCL-Pad28)") (class "Default")
      (node (ref "U2") (pin "28") (pinfunction "P1[31]/USB_OVRCR2n/SSP1_SCK/ADC0_IN[5]/I2C0_SCL_28") (pintype "passive"))
    )
    (net (code "109") (name "unconnected-(U2-P2[3]{slash}PWM1[4]{slash}U1_DCD{slash}T2_MAT2{slash}TRACEDATA[2]{slash}LCD_FP-Pad100)") (class "Default")
      (node (ref "U2") (pin "100") (pinfunction "P2[3]/PWM1[4]/U1_DCD/T2_MAT2/TRACEDATA[2]/LCD_FP_100") (pintype "passive"))
    )
    (net (code "110") (name "unconnected-(U2-P2[7]{slash}CAN_RD2{slash}U1_RTS{slash}LCD_VD[1]{slash}LCD_VD[5]-Pad95)") (class "Default")
      (node (ref "U2") (pin "95") (pinfunction "P2[7]/CAN_RD2/U1_RTS/LCD_VD[1]/LCD_VD[5]_95") (pintype "passive"))
    )
    (net (code "111") (name "unconnected-(U2-P4[2]{slash}EMC_A[2]-Pad58)") (class "Default")
      (node (ref "U2") (pin "58") (pinfunction "P4[2]/EMC_A[2]_58") (pintype "passive"))
    )
    (net (code "112") (name "unconnected-(U2-P4[6]{slash}EMC_A[6]-Pad78)") (class "Default")
      (node (ref "U2") (pin "78") (pinfunction "P4[6]/EMC_A[6]_78") (pintype "passive"))
    )
    (net (code "113") (name "unconnected-(U2-P4[7]{slash}EMC_A[7]-Pad84)") (class "Default")
      (node (ref "U2") (pin "84") (pinfunction "P4[7]/EMC_A[7]_84") (pintype "passive"))
    )
    (net (code "114") (name "unconnected-(U2-P4[8]{slash}EMC_A[8]-Pad88)") (class "Default")
      (node (ref "U2") (pin "88") (pinfunction "P4[8]/EMC_A[8]_88") (pintype "passive"))
    )
    (net (code "115") (name "unconnected-(U2-P4[9]{slash}EMC_A[9]-Pad91)") (class "Default")
      (node (ref "U2") (pin "91") (pinfunction "P4[9]/EMC_A[9]_91") (pintype "passive"))
    )
    (net (code "116") (name "unconnected-(U2-P4[10]{slash}EMC_A[10]-Pad94)") (class "Default")
      (node (ref "U2") (pin "94") (pinfunction "P4[10]/EMC_A[10]_94") (pintype "passive"))
    )
    (net (code "117") (name "unconnected-(U2-P4[11]{slash}EMC_A[11]-Pad101)") (class "Default")
      (node (ref "U2") (pin "101") (pinfunction "P4[11]/EMC_A[11]_101") (pintype "passive"))
    )
    (net (code "118") (name "unconnected-(U2-P4[12]{slash}EMC_A[12]-Pad104)") (class "Default")
      (node (ref "U2") (pin "104") (pinfunction "P4[12]/EMC_A[12]_104") (pintype "passive"))
    )
    (net (code "119") (name "unconnected-(U2-P4[15]{slash}EMC_A[15]-Pad120)") (class "Default")
      (node (ref "U2") (pin "120") (pinfunction "P4[15]/EMC_A[15]_120") (pintype "passive"))
    )
    (net (code "120") (name "unconnected-(U2-P4[24]{slash}~{EMC_OE}-Pad127)") (class "Default")
      (node (ref "U2") (pin "127") (pinfunction "P4[24]/~{EMC_OE}_127") (pintype "passive"))
    )
    (net (code "121") (name "unconnected-(U2-P4[25]{slash}~{EMC_WE}-Pad124)") (class "Default")
      (node (ref "U2") (pin "124") (pinfunction "P4[25]/~{EMC_WE}_124") (pintype "passive"))
    )
    (net (code "122") (name "unconnected-(U2-P4[28]{slash}~{EMC_BLS2}{slash}U3_TXD{slash}T2_MAT0{slash}LCD_VD[6]{slash}LCD_VD[10]{slash}LCD_VD[2]-Pad118)") (class "Default")
      (node (ref "U2") (pin "118") (pinfunction "P4[28]/~{EMC_BLS2}/U3_TXD/T2_MAT0/LCD_VD[6]/LCD_VD[10]/LCD_VD[2]_118") (pintype "passive"))
    )
    (net (code "123") (name "unconnected-(U2-P4[29]{slash}~{EMC_BLS3}{slash}U3_RXD{slash}T2_MAT1{slash}I2C2_SCL{slash}LCD_VD[7]{slash}LCD_VD[11]{slash}LCD_VD[3]-Pad122)") (class "Default")
      (node (ref "U2") (pin "122") (pinfunction "P4[29]/~{EMC_BLS3}/U3_RXD/T2_MAT1/I2C2_SCL/LCD_VD[7]/LCD_VD[11]/LCD_VD[3]_122") (pintype "passive"))
    )
    (net (code "124") (name "unconnected-(U2-P4[30]{slash}~{EMC_CS0}-Pad130)") (class "Default")
      (node (ref "U2") (pin "130") (pinfunction "P4[30]/~{EMC_CS0}_130") (pintype "passive"))
    )
    (net (code "125") (name "unconnected-(U2-P5[0]{slash}EMC_A[24]{slash}SSP2_MOSI{slash}T2_MAT2-Pad6)") (class "Default")
      (node (ref "U2") (pin "6") (pinfunction "P5[0]/EMC_A[24]/SSP2_MOSI/T2_MAT2_6") (pintype "passive"))
    )
    (net (code "126") (name "unconnected-(U2-P5[1]{slash}EMC_A[25]{slash}SSP2_MISO{slash}T2_MAT3-Pad21)") (class "Default")
      (node (ref "U2") (pin "21") (pinfunction "P5[1]/EMC_A[25]/SSP2_MISO/T2_MAT3_21") (pintype "passive"))
    )
    (net (code "127") (name "unconnected-(U2-P5[2]{slash}T2_MAT2{slash}I2C0_SDA-Pad81)") (class "Default")
      (node (ref "U2") (pin "81") (pinfunction "P5[2]/T2_MAT2/I2C0_SDA_81") (pintype "passive"))
    )
    (net (code "128") (name "unconnected-(U2-P5[3]{slash}U4_RXD{slash}I2C0_SCL-Pad98)") (class "Default")
      (node (ref "U2") (pin "98") (pinfunction "P5[3]/U4_RXD/I2C0_SCL_98") (pintype "passive"))
    )
    (net (code "129") (name "unconnected-(U2-RTCX1{slash}-Pad23)") (class "Default")
      (node (ref "U2") (pin "23") (pinfunction "RTCX1/_23") (pintype "passive"))
    )
    (net (code "130") (name "unconnected-(U2-RTCX2{slash}-Pad25)") (class "Default")
      (node (ref "U2") (pin "25") (pinfunction "RTCX2/_25") (pintype "passive"))
    )
    (net (code "131") (name "unconnected-(U2-RTC_ALARM{slash}-Pad26)") (class "Default")
      (node (ref "U2") (pin "26") (pinfunction "RTC_ALARM/_26") (pintype "passive"))
    )
    (net (code "132") (name "unconnected-(U2-USB_D2--Pad37)") (class "Default")
      (node (ref "U2") (pin "37") (pinfunction "USB_D2-_37") (pintype "passive+no_connect"))
    )
    (net (code "133") (name "unconnected-(U2-VABT{slash}-Pad27)") (class "Default")
      (node (ref "U2") (pin "27") (pinfunction "VABT/_27") (pintype "passive"))
    )
    (net (code "134") (name "unconnected-(U2-~{RSTOUT}-Pad20)") (class "Default")
      (node (ref "U2") (pin "20") (pinfunction "~{RSTOUT}_20") (pintype "passive+no_connect"))
    )
  )
)
